# RoBeast_Mounting_Shield.net
KiCad netlist of a schematic drawn in Altium Designer
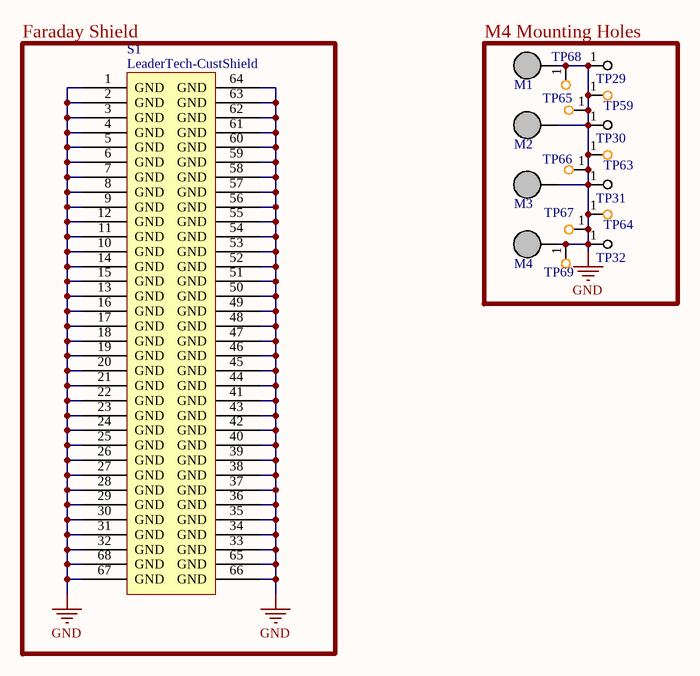
[diagram p0: RoBeast_Mounting_Shield.SchDoc]

(export (version "E")
  (design (tool "Eeschema 10.0.6"))
  (components
    (comp (ref "M1")
      (value "M4 Mounting Screw Hole")
      (footprint "M4")
      (libsource (lib "RoBeast_Schematic_Library") (part "M4"))
    )
    (comp (ref "M2")
      (value "M4 Mounting Screw Hole")
      (footprint "M4")
      (libsource (lib "RoBeast_Schematic_Library") (part "M4"))
    )
    (comp (ref "M3")
      (value "M4 Mounting Screw Hole")
      (footprint "M4")
      (libsource (lib "RoBeast_Schematic_Library") (part "M4"))
    )
    (comp (ref "M4")
      (value "M4 Mounting Screw Hole")
      (footprint "M4")
      (libsource (lib "RoBeast_Schematic_Library") (part "M4"))
    )
    (comp (ref "S1")
      (value "LeaderTech-CustShield")
      (footprint "CMP-00028-00007-1")
      (libsource (lib "RoBeast_Schematic_Library") (part "CMP-00028-00007-1"))
    )
    (comp (ref "TP29")
      (value "Test Point")
      (footprint "RCWCTE")
      (description "Testing/Accessories")
      (fields (field (name "MANUFACTURER") "KOA Speer") (field (name "MANUFACTURER PART NUMBER") "RCWCTE"))
      (libsource (lib "RoBeast_Schematic_Library") (part "RCWCTE"))
    )
    (comp (ref "TP30")
      (value "Test Point")
      (footprint "RCWCTE")
      (description "Testing/Accessories")
      (fields (field (name "MANUFACTURER") "KOA Speer") (field (name "MANUFACTURER PART NUMBER") "RCWCTE"))
      (libsource (lib "RoBeast_Schematic_Library") (part "RCWCTE"))
    )
    (comp (ref "TP31")
      (value "Test Point")
      (footprint "RCWCTE")
      (description "Testing/Accessories")
      (fields (field (name "MANUFACTURER") "KOA Speer") (field (name "MANUFACTURER PART NUMBER") "RCWCTE"))
      (libsource (lib "RoBeast_Schematic_Library") (part "RCWCTE"))
    )
    (comp (ref "TP32")
      (value "Test Point")
      (footprint "RCWCTE")
      (description "Testing/Accessories")
      (fields (field (name "MANUFACTURER") "KOA Speer") (field (name "MANUFACTURER PART NUMBER") "RCWCTE"))
      (libsource (lib "RoBeast_Schematic_Library") (part "RCWCTE"))
    )
    (comp (ref "TP59")
      (value "Test Point")
      (footprint "Test Point")
      (libsource (lib "RoBeast_Schematic_Library") (part "Test Point"))
    )
    (comp (ref "TP63")
      (value "Test Point")
      (footprint "Test Point")
      (libsource (lib "RoBeast_Schematic_Library") (part "Test Point"))
    )
    (comp (ref "TP64")
      (value "Test Point")
      (footprint "Test Point")
      (libsource (lib "RoBeast_Schematic_Library") (part "Test Point"))
    )
    (comp (ref "TP65")
      (value "Test Point")
      (footprint "Test Point")
      (libsource (lib "RoBeast_Schematic_Library") (part "Test Point"))
    )
    (comp (ref "TP66")
      (value "Test Point")
      (footprint "Test Point")
      (libsource (lib "RoBeast_Schematic_Library") (part "Test Point"))
    )
    (comp (ref "TP67")
      (value "Test Point")
      (footprint "Test Point")
      (libsource (lib "RoBeast_Schematic_Library") (part "Test Point"))
    )
    (comp (ref "TP68")
      (value "Test Point")
      (footprint "Test Point")
      (libsource (lib "RoBeast_Schematic_Library") (part "Test Point"))
    )
    (comp (ref "TP69")
      (value "Test Point")
      (footprint "Test Point")
      (libsource (lib "RoBeast_Schematic_Library") (part "Test Point"))
    )
  )
  (nets
    (net (code "1") (name "GND") (class "Default")
      (node (ref "M1") (pin "1") (pinfunction "M4_1") (pintype "passive"))
      (node (ref "M2") (pin "1") (pinfunction "M4_1") (pintype "passive"))
      (node (ref "M3") (pin "1") (pinfunction "M4_1") (pintype "passive"))
      (node (ref "M4") (pin "1") (pinfunction "M4_1") (pintype "passive"))
      (node (ref "S1") (pin "1") (pinfunction "GND_1") (pintype "passive"))
      (node (ref "S1") (pin "10") (pinfunction "GND_10") (pintype "passive"))
      (node (ref "S1") (pin "11") (pinfunction "GND_11") (pintype "passive"))
      (node (ref "S1") (pin "12") (pinfunction "GND_12") (pintype "passive"))
      (node (ref "S1") (pin "13") (pinfunction "GND_13") (pintype "passive"))
      (node (ref "S1") (pin "14") (pinfunction "GND_14") (pintype "passive"))
      (node (ref "S1") (pin "15") (pinfunction "GND_15") (pintype "passive"))
      (node (ref "S1") (pin "16") (pinfunction "GND_16") (pintype "passive"))
      (node (ref "S1") (pin "17") (pinfunction "GND_17") (pintype "passive"))
      (node (ref "S1") (pin "18") (pinfunction "GND_18") (pintype "passive"))
      (node (ref "S1") (pin "19") (pinfunction "GND_19") (pintype "passive"))
      (node (ref "S1") (pin "2") (pinfunction "GND_2") (pintype "passive"))
      (node (ref "S1") (pin "20") (pinfunction "GND_20") (pintype "passive"))
      (node (ref "S1") (pin "21") (pinfunction "GND_21") (pintype "passive"))
      (node (ref "S1") (pin "22") (pinfunction "GND_22") (pintype "passive"))
      (node (ref "S1") (pin "23") (pinfunction "GND_23") (pintype "passive"))
      (node (ref "S1") (pin "24") (pinfunction "GND_24") (pintype "passive"))
      (node (ref "S1") (pin "25") (pinfunction "GND_25") (pintype "passive"))
      (node (ref "S1") (pin "26") (pinfunction "GND_26") (pintype "passive"))
      (node (ref "S1") (pin "27") (pinfunction "GND_27") (pintype "passive"))
      (node (ref "S1") (pin "28") (pinfunction "GND_28") (pintype "passive"))
      (node (ref "S1") (pin "29") (pinfunction "GND_29") (pintype "passive"))
      (node (ref "S1") (pin "3") (pinfunction "GND_3") (pintype "passive"))
      (node (ref "S1") (pin "30") (pinfunction "GND_30") (pintype "passive"))
      (node (ref "S1") (pin "31") (pinfunction "GND_31") (pintype "passive"))
      (node (ref "S1") (pin "32") (pinfunction "GND_32") (pintype "passive"))
      (node (ref "S1") (pin "33") (pinfunction "GND_33") (pintype "passive"))
      (node (ref "S1") (pin "34") (pinfunction "GND_34") (pintype "passive"))
      (node (ref "S1") (pin "35") (pinfunction "GND_35") (pintype "passive"))
      (node (ref "S1") (pin "36") (pinfunction "GND_36") (pintype "passive"))
      (node (ref "S1") (pin "37") (pinfunction "GND_37") (pintype "passive"))
      (node (ref "S1") (pin "38") (pinfunction "GND_38") (pintype "passive"))
      (node (ref "S1") (pin "39") (pinfunction "GND_39") (pintype "passive"))
      (node (ref "S1") (pin "4") (pinfunction "GND_4") (pintype "passive"))
      (node (ref "S1") (pin "40") (pinfunction "GND_40") (pintype "passive"))
      (node (ref "S1") (pin "41") (pinfunction "GND_41") (pintype "passive"))
      (node (ref "S1") (pin "42") (pinfunction "GND_42") (pintype "passive"))
      (node (ref "S1") (pin "43") (pinfunction "GND_43") (pintype "passive"))
      (node (ref "S1") (pin "44") (pinfunction "GND_44") (pintype "passive"))
      (node (ref "S1") (pin "45") (pinfunction "GND_45") (pintype "passive"))
      (node (ref "S1") (pin "46") (pinfunction "GND_46") (pintype "passive"))
      (node (ref "S1") (pin "47") (pinfunction "GND_47") (pintype "passive"))
      (node (ref "S1") (pin "48") (pinfunction "GND_48") (pintype "passive"))
      (node (ref "S1") (pin "49") (pinfunction "GND_49") (pintype "passive"))
      (node (ref "S1") (pin "5") (pinfunction "GND_5") (pintype "passive"))
      (node (ref "S1") (pin "50") (pinfunction "GND_50") (pintype "passive"))
      (node (ref "S1") (pin "51") (pinfunction "GND_51") (pintype "passive"))
      (node (ref "S1") (pin "52") (pinfunction "GND_52") (pintype "passive"))
      (node (ref "S1") (pin "53") (pinfunction "GND_53") (pintype "passive"))
      (node (ref "S1") (pin "54") (pinfunction "GND_54") (pintype "passive"))
      (node (ref "S1") (pin "55") (pinfunction "GND_55") (pintype "passive"))
      (node (ref "S1") (pin "56") (pinfunction "GND_56") (pintype "passive"))
      (node (ref "S1") (pin "57") (pinfunction "GND_57") (pintype "passive"))
      (node (ref "S1") (pin "58") (pinfunction "GND_58") (pintype "passive"))
      (node (ref "S1") (pin "59") (pinfunction "GND_59") (pintype "passive"))
      (node (ref "S1") (pin "6") (pinfunction "GND_6") (pintype "passive"))
      (node (ref "S1") (pin "60") (pinfunction "GND_60") (pintype "passive"))
      (node (ref "S1") (pin "61") (pinfunction "GND_61") (pintype "passive"))
      (node (ref "S1") (pin "62") (pinfunction "GND_62") (pintype "passive"))
      (node (ref "S1") (pin "63") (pinfunction "GND_63") (pintype "passive"))
      (node (ref "S1") (pin "64") (pinfunction "GND_64") (pintype "passive"))
      (node (ref "S1") (pin "65") (pinfunction "GND_65") (pintype "passive"))
      (node (ref "S1") (pin "66") (pinfunction "GND_66") (pintype "passive"))
      (node (ref "S1") (pin "67") (pinfunction "GND_67") (pintype "passive"))
      (node (ref "S1") (pin "68") (pinfunction "GND_68") (pintype "passive"))
      (node (ref "S1") (pin "7") (pinfunction "GND_7") (pintype "passive"))
      (node (ref "S1") (pin "8") (pinfunction "GND_8") (pintype "passive"))
      (node (ref "S1") (pin "9") (pinfunction "GND_9") (pintype "passive"))
      (node (ref "TP29") (pin "1") (pinfunction "1_1") (pintype "passive"))
      (node (ref "TP30") (pin "1") (pinfunction "1_1") (pintype "passive"))
      (node (ref "TP31") (pin "1") (pinfunction "1_1") (pintype "passive"))
      (node (ref "TP32") (pin "1") (pinfunction "1_1") (pintype "passive"))
      (node (ref "TP59") (pin "1") (pinfunction "1_1") (pintype "passive"))
      (node (ref "TP63") (pin "1") (pinfunction "1_1") (pintype "passive"))
      (node (ref "TP64") (pin "1") (pinfunction "1_1") (pintype "passive"))
      (node (ref "TP65") (pin "1") (pinfunction "1_1") (pintype "passive"))
      (node (ref "TP66") (pin "1") (pinfunction "1_1") (pintype "passive"))
      (node (ref "TP67") (pin "1") (pinfunction "1_1") (pintype "passive"))
      (node (ref "TP68") (pin "1") (pinfunction "1_1") (pintype "passive"))
      (node (ref "TP69") (pin "1") (pinfunction "1_1") (pintype "passive"))
    )
  )
)
